# AB_Amplifier.net
KiCad netlist of a schematic drawn in Altium Designer
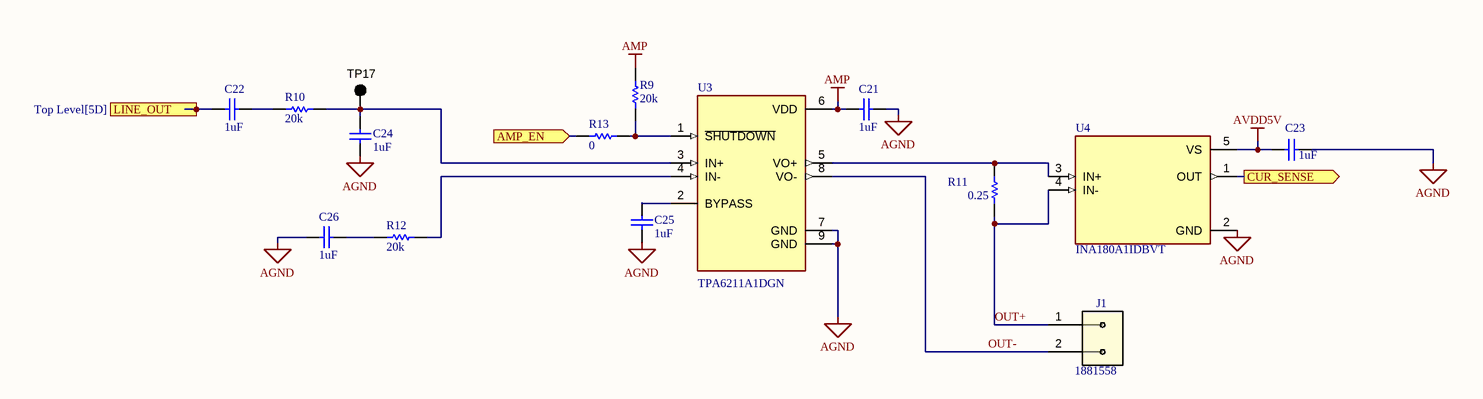
[diagram p0: AB Amplifier.SchDoc]

(export (version "E")
  (design (tool "Eeschema 10.0.6"))
  (components
    (comp (ref "C21") (value "1uF") (footprint "0603") (libsource (lib "SamlibSCH") (part "C TBD 0603")))
    (comp (ref "C22") (value "1uF") (footprint "0603") (libsource (lib "SamlibSCH") (part "C TBD 0603")))
    (comp (ref "C23") (value "1uF") (footprint "0603") (libsource (lib "SamlibSCH") (part "C TBD 0603")))
    (comp (ref "C24") (value "1uF") (footprint "0603") (libsource (lib "SamlibSCH") (part "C TBD 0603")))
    (comp (ref "C25") (value "1uF") (footprint "0603") (libsource (lib "SamlibSCH") (part "C TBD 0603")))
    (comp (ref "C26") (value "1uF") (footprint "0603") (libsource (lib "SamlibSCH") (part "C TBD 0603")))
    (comp (ref "J1") (value "1881558") (footprint "1881558") (libsource (lib "Schlib1") (part "1881558")))
    (comp (ref "R9") (value "20k") (footprint "0603") (libsource (lib "SamlibSCH") (part "R TBD 0603")))
    (comp (ref "R10") (value "20k") (footprint "0603") (libsource (lib "SamlibSCH") (part "R TBD 0603")))
    (comp (ref "R11") (value "0.25") (footprint "0805_HV") (libsource (lib "SamlibSCH") (part "R TBD 0805")))
    (comp (ref "R12") (value "20k") (footprint "0603") (libsource (lib "SamlibSCH") (part "R TBD 0603")))
    (comp (ref "R13") (value "0") (footprint "0603") (libsource (lib "SamlibSCH") (part "R TBD 0603")))
    (comp (ref "TP17")
      (value "5001")
      (footprint "Testpoint pad")
      (description "TEST POINT PC MINI .040\"D BLACK")
      (fields (field (name "MANUFACTURER") "Keystone Electronics"))
      (libsource (lib "SamlibSCH") (part "5001"))
    )
    (comp (ref "U3")
      (value "TPA6211A1DGN")
      (footprint "SOP65P490X110-9N")
      (description "3.1-W, mono, analog input Class-AB audio amplifier")
      (fields (field (name "MF") "Texas Instruments"))
      (libsource (lib "Schlib1") (part "TPA6211A1DGN"))
    )
    (comp (ref "U4")
      (value "INA180A1IDBVT")
      (footprint "SOT95P280X145-5N")
      (description "26V, 350kHz current sense amplifier")
      (fields (field (name "MF") "Texas Instruments"))
      (libsource (lib "Schlib1") (part "INA180A1IDBVT"))
    )
  )
  (nets
    (net (code "1") (name "/AMP_EN") (class "Default")
      (node (ref "R13") (pin "2") (pinfunction "2_2") (pintype "passive"))
    )
    (net (code "2") (name "/CUR_SENSE") (class "Default")
      (node (ref "U4") (pin "1") (pinfunction "OUT_1") (pintype "output"))
    )
    (net (code "3") (name "/LINE_OUT") (class "Default")
      (node (ref "C22") (pin "1") (pinfunction "1_1") (pintype "passive"))
    )
    (net (code "4") (name "/OUT+") (class "Default")
      (node (ref "J1") (pin "1") (pinfunction "1_1") (pintype "passive"))
      (node (ref "R11") (pin "1") (pinfunction "1_1") (pintype "passive"))
      (node (ref "U4") (pin "4") (pinfunction "IN-_4") (pintype "input"))
    )
    (net (code "5") (name "/OUT-") (class "Default")
      (node (ref "J1") (pin "2") (pinfunction "2_2") (pintype "passive"))
      (node (ref "U3") (pin "8") (pinfunction "VO-_8") (pintype "output"))
    )
    (net (code "6") (name "AGND") (class "Default")
      (node (ref "C21") (pin "1") (pinfunction "1_1") (pintype "passive"))
      (node (ref "C23") (pin "1") (pinfunction "1_1") (pintype "passive"))
      (node (ref "C24") (pin "1") (pinfunction "1_1") (pintype "passive"))
      (node (ref "C25") (pin "1") (pinfunction "1_1") (pintype "passive"))
      (node (ref "C26") (pin "1") (pinfunction "1_1") (pintype "passive"))
      (node (ref "U3") (pin "7") (pinfunction "GND_7") (pintype "power_in"))
      (node (ref "U3") (pin "9") (pinfunction "GND_9") (pintype "power_in"))
      (node (ref "U4") (pin "2") (pinfunction "GND_2") (pintype "power_in"))
    )
    (net (code "7") (name "AMP") (class "Default")
      (node (ref "C21") (pin "2") (pinfunction "2_2") (pintype "passive"))
      (node (ref "R9") (pin "2") (pinfunction "2_2") (pintype "passive"))
      (node (ref "U3") (pin "6") (pinfunction "VDD_6") (pintype "power_in"))
    )
    (net (code "8") (name "AVDD5V") (class "Default")
      (node (ref "C23") (pin "2") (pinfunction "2_2") (pintype "passive"))
      (node (ref "U4") (pin "5") (pinfunction "VS_5") (pintype "power_in"))
    )
    (net (code "9") (name "Net-(C22-Pad2)") (class "Default")
      (node (ref "C22") (pin "2") (pinfunction "2_2") (pintype "passive"))
      (node (ref "R10") (pin "1") (pinfunction "1_1") (pintype "passive"))
    )
    (net (code "10") (name "Net-(C26-Pad2)") (class "Default")
      (node (ref "C26") (pin "2") (pinfunction "2_2") (pintype "passive"))
      (node (ref "R12") (pin "1") (pinfunction "1_1") (pintype "passive"))
    )
    (net (code "11") (name "Net-(U3-BYPASS)") (class "Default")
      (node (ref "C25") (pin "2") (pinfunction "2_2") (pintype "passive"))
      (node (ref "U3") (pin "2") (pinfunction "BYPASS_2") (pintype "passive"))
    )
    (net (code "12") (name "Net-(U3-IN+)") (class "Default")
      (node (ref "C24") (pin "2") (pinfunction "2_2") (pintype "passive"))
      (node (ref "R10") (pin "2") (pinfunction "2_2") (pintype "passive"))
      (node (ref "TP17") (pin "1") (pintype "passive"))
      (node (ref "U3") (pin "3") (pinfunction "IN+_3") (pintype "input"))
    )
    (net (code "13") (name "Net-(U3-IN-)") (class "Default")
      (node (ref "R12") (pin "2") (pinfunction "2_2") (pintype "passive"))
      (node (ref "U3") (pin "4") (pinfunction "IN-_4") (pintype "input"))
    )
    (net (code "14") (name "Net-(U3-VO+)") (class "Default")
      (node (ref "R11") (pin "2") (pinfunction "2_2") (pintype "passive"))
      (node (ref "U3") (pin "5") (pinfunction "VO+_5") (pintype "output"))
      (node (ref "U4") (pin "3") (pinfunction "IN+_3") (pintype "input"))
    )
    (net (code "15") (name "Net-(U3-~{SHUTDOWN})") (class "Default")
      (node (ref "R13") (pin "1") (pinfunction "1_1") (pintype "passive"))
      (node (ref "R9") (pin "1") (pinfunction "1_1") (pintype "passive"))
      (node (ref "U3") (pin "1") (pinfunction "~{SHUTDOWN}_1") (pintype "input"))
    )
  )
)
